# Adafruit_Speaker_Bonnet_rev_C.net
KiCad netlist of a schematic drawn in EAGLE
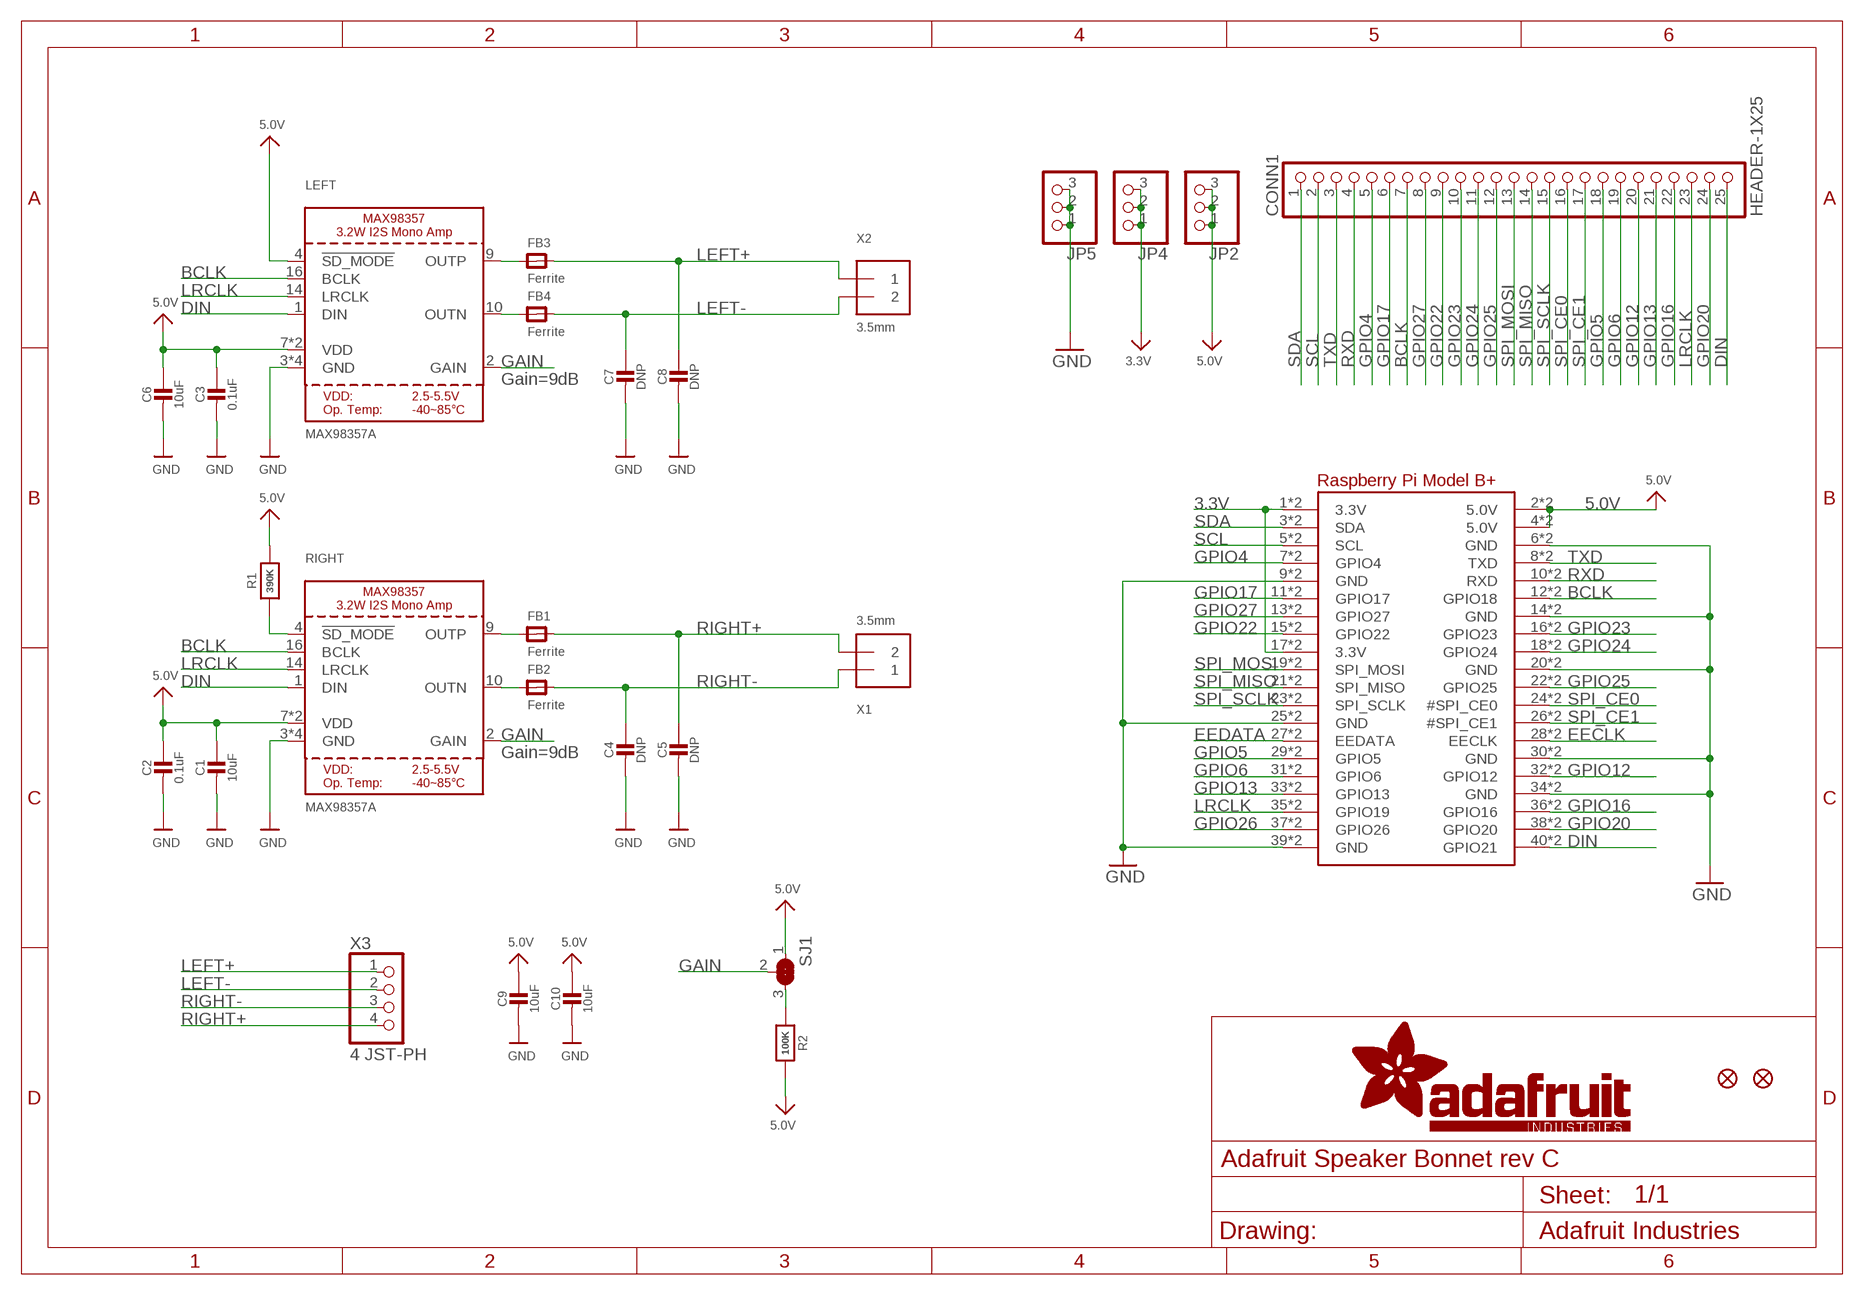
[diagram p0: schematic, sheet 1]

(export (version "E")
  (design (tool "Eeschema 10.0.6"))
  (components
    (comp (ref "C1")
      (value "10uF")
      (footprint "eagle-import:0805-NO")
      (libsource (lib "eagle-import") (part "CAP_CERAMIC0805-NOOUTLINE"))
    )
    (comp (ref "C2")
      (value "0.1uF")
      (footprint "eagle-import:0805-NO")
      (libsource (lib "eagle-import") (part "CAP_CERAMIC0805-NOOUTLINE"))
    )
    (comp (ref "C3")
      (value "0.1uF")
      (footprint "eagle-import:0805-NO")
      (libsource (lib "eagle-import") (part "CAP_CERAMIC0805-NOOUTLINE"))
    )
    (comp (ref "C4")
      (value "DNP")
      (footprint "eagle-import:0805-NO")
      (libsource (lib "eagle-import") (part "CAP_CERAMIC0805-NOOUTLINE"))
    )
    (comp (ref "C5")
      (value "DNP")
      (footprint "eagle-import:0805-NO")
      (libsource (lib "eagle-import") (part "CAP_CERAMIC0805-NOOUTLINE"))
    )
    (comp (ref "C6")
      (value "10uF")
      (footprint "eagle-import:0805-NO")
      (libsource (lib "eagle-import") (part "CAP_CERAMIC0805-NOOUTLINE"))
    )
    (comp (ref "C7")
      (value "DNP")
      (footprint "eagle-import:0805-NO")
      (libsource (lib "eagle-import") (part "CAP_CERAMIC0805-NOOUTLINE"))
    )
    (comp (ref "C8")
      (value "DNP")
      (footprint "eagle-import:0805-NO")
      (libsource (lib "eagle-import") (part "CAP_CERAMIC0805-NOOUTLINE"))
    )
    (comp (ref "C9")
      (value "10uF")
      (footprint "eagle-import:0805-NO")
      (libsource (lib "eagle-import") (part "CAP_CERAMIC0805-NOOUTLINE"))
    )
    (comp (ref "C10")
      (value "10uF")
      (footprint "eagle-import:0805-NO")
      (libsource (lib "eagle-import") (part "CAP_CERAMIC0805-NOOUTLINE"))
    )
    (comp (ref "CONN1")
      (value "HEADER-1X25")
      (footprint "eagle-import:1X25_ROUND_70MIL")
      (libsource (lib "eagle-import") (part "HEADER-1X25"))
    )
    (comp (ref "FB1")
      (value "Ferrite")
      (footprint "eagle-import:0805-NO")
      (libsource (lib "eagle-import") (part "FERRITE-0805NO"))
    )
    (comp (ref "FB2")
      (value "Ferrite")
      (footprint "eagle-import:0805-NO")
      (libsource (lib "eagle-import") (part "FERRITE-0805NO"))
    )
    (comp (ref "FB3")
      (value "Ferrite")
      (footprint "eagle-import:0805-NO")
      (libsource (lib "eagle-import") (part "FERRITE-0805NO"))
    )
    (comp (ref "FB4")
      (value "Ferrite")
      (footprint "eagle-import:0805-NO")
      (libsource (lib "eagle-import") (part "FERRITE-0805NO"))
    )
    (comp (ref "FID1")
      (value "FIDUCIAL_1MM")
      (footprint "eagle-import:FIDUCIAL_1MM")
      (libsource (lib "eagle-import") (part "FIDUCIAL_1MM"))
    )
    (comp (ref "FID2")
      (value "FIDUCIAL_1MM")
      (footprint "eagle-import:FIDUCIAL_1MM")
      (libsource (lib "eagle-import") (part "FIDUCIAL_1MM"))
    )
    (comp (ref "JP2")
      (value "HEADER-1X376MIL")
      (footprint "eagle-import:1X03_ROUND_76")
      (libsource (lib "eagle-import") (part "HEADER-1X376MIL"))
    )
    (comp (ref "JP4")
      (value "HEADER-1X376MIL")
      (footprint "eagle-import:1X03_ROUND_76")
      (libsource (lib "eagle-import") (part "HEADER-1X376MIL"))
    )
    (comp (ref "JP5")
      (value "HEADER-1X376MIL")
      (footprint "eagle-import:1X03_ROUND_76")
      (libsource (lib "eagle-import") (part "HEADER-1X376MIL"))
    )
    (comp (ref "LEFT")
      (value "MAX98357A")
      (footprint "eagle-import:QFN16_3MM")
      (libsource (lib "eagle-import") (part "AUDIOAMP_MAX98357"))
    )
    (comp (ref "R1")
      (value "390K")
      (footprint "eagle-import:0805-NO")
      (libsource (lib "eagle-import") (part "RESISTOR0805_NOOUTLINE"))
    )
    (comp (ref "R2")
      (value "100K")
      (footprint "eagle-import:0805-NO")
      (libsource (lib "eagle-import") (part "RESISTOR0805_NOOUTLINE"))
    )
    (comp (ref "RIGHT")
      (value "MAX98357A")
      (footprint "eagle-import:QFN16_3MM")
      (libsource (lib "eagle-import") (part "AUDIOAMP_MAX98357"))
    )
    (comp (ref "RPI1")
      (value "RASPBERRYPI_BPLUS_BONNET_THMSMT")
      (footprint "eagle-import:PI_BONNET_THMSMT")
      (libsource (lib "eagle-import") (part "RASPBERRYPI_BPLUS_BONNET_THMSMT"))
    )
    (comp (ref "SJ1")
      (value "SOLDERJUMPER_2WAY")
      (footprint "eagle-import:SOLDERJUMPER_2WAY_OPEN_NOPASTE")
      (libsource (lib "eagle-import") (part "SOLDERJUMPER_2WAY"))
    )
    (comp (ref "X1")
      (value "3.5mm")
      (footprint "eagle-import:TERMBLOCK_1X2-3.5MM")
      (libsource (lib "eagle-import") (part "TERMBLOCK_1X2"))
    )
    (comp (ref "X2")
      (value "3.5mm")
      (footprint "eagle-import:TERMBLOCK_1X2-3.5MM")
      (libsource (lib "eagle-import") (part "TERMBLOCK_1X2"))
    )
    (comp (ref "X3")
      (value "4 JST-PH")
      (footprint "eagle-import:JSTPH4")
      (libsource (lib "eagle-import") (part "CON_JST_PH_4PIN"))
    )
  )
  (nets
    (net (code "1") (name "/BCLK") (class "Default")
      (node (ref "CONN1") (pin "7") (pinfunction "7_7") (pintype "passive"))
      (node (ref "LEFT") (pin "16") (pinfunction "BCLK_16") (pintype "bidirectional"))
      (node (ref "RIGHT") (pin "16") (pinfunction "BCLK_16") (pintype "bidirectional"))
      (node (ref "RPI1") (pin "12") (pinfunction "GPIO18_12") (pintype "bidirectional"))
      (node (ref "RPI1") (pin "S12") (pinfunction "GPIO18_S12") (pintype "bidirectional"))
    )
    (net (code "2") (name "/DIN") (class "Default")
      (node (ref "CONN1") (pin "25") (pinfunction "25_25") (pintype "passive"))
      (node (ref "LEFT") (pin "1") (pinfunction "DIN_1") (pintype "bidirectional"))
      (node (ref "RIGHT") (pin "1") (pinfunction "DIN_1") (pintype "bidirectional"))
      (node (ref "RPI1") (pin "40") (pinfunction "GPIO21_40") (pintype "bidirectional"))
      (node (ref "RPI1") (pin "S40") (pinfunction "GPIO21_S40") (pintype "bidirectional"))
    )
    (net (code "3") (name "/EECLK") (class "Default")
      (node (ref "RPI1") (pin "28") (pinfunction "EECLK_28") (pintype "bidirectional"))
      (node (ref "RPI1") (pin "S28") (pinfunction "EECLK_S28") (pintype "bidirectional"))
    )
    (net (code "4") (name "/EEDATA") (class "Default")
      (node (ref "RPI1") (pin "27") (pinfunction "EEDATA_27") (pintype "bidirectional"))
      (node (ref "RPI1") (pin "S27") (pinfunction "EEDATA_S27") (pintype "bidirectional"))
    )
    (net (code "5") (name "/GAIN") (class "Default")
      (node (ref "LEFT") (pin "2") (pinfunction "GAIN_2") (pintype "bidirectional"))
      (node (ref "RIGHT") (pin "2") (pinfunction "GAIN_2") (pintype "bidirectional"))
      (node (ref "SJ1") (pin "2") (pinfunction "2_2") (pintype "passive"))
    )
    (net (code "6") (name "/GPIO4") (class "Default")
      (node (ref "CONN1") (pin "5") (pinfunction "5_5") (pintype "passive"))
      (node (ref "RPI1") (pin "7") (pinfunction "GPIO4_7") (pintype "bidirectional"))
      (node (ref "RPI1") (pin "S7") (pinfunction "GPIO4_S7") (pintype "bidirectional"))
    )
    (net (code "7") (name "/GPIO5") (class "Default")
      (node (ref "CONN1") (pin "18") (pinfunction "18_18") (pintype "passive"))
      (node (ref "RPI1") (pin "29") (pinfunction "GPIO5_29") (pintype "bidirectional"))
      (node (ref "RPI1") (pin "S29") (pinfunction "GPIO5_S29") (pintype "bidirectional"))
    )
    (net (code "8") (name "/GPIO6") (class "Default")
      (node (ref "CONN1") (pin "19") (pinfunction "19_19") (pintype "passive"))
      (node (ref "RPI1") (pin "31") (pinfunction "GPIO6_31") (pintype "bidirectional"))
      (node (ref "RPI1") (pin "S31") (pinfunction "GPIO6_S31") (pintype "bidirectional"))
    )
    (net (code "9") (name "/GPIO12") (class "Default")
      (node (ref "CONN1") (pin "20") (pinfunction "20_20") (pintype "passive"))
      (node (ref "RPI1") (pin "32") (pinfunction "GPIO12_32") (pintype "bidirectional"))
      (node (ref "RPI1") (pin "S32") (pinfunction "GPIO12_S32") (pintype "bidirectional"))
    )
    (net (code "10") (name "/GPIO13") (class "Default")
      (node (ref "CONN1") (pin "21") (pinfunction "21_21") (pintype "passive"))
      (node (ref "RPI1") (pin "33") (pinfunction "GPIO13_33") (pintype "bidirectional"))
      (node (ref "RPI1") (pin "S33") (pinfunction "GPIO13_S33") (pintype "bidirectional"))
    )
    (net (code "11") (name "/GPIO16") (class "Default")
      (node (ref "CONN1") (pin "22") (pinfunction "22_22") (pintype "passive"))
      (node (ref "RPI1") (pin "36") (pinfunction "GPIO16_36") (pintype "bidirectional"))
      (node (ref "RPI1") (pin "S36") (pinfunction "GPIO16_S36") (pintype "bidirectional"))
    )
    (net (code "12") (name "/GPIO17") (class "Default")
      (node (ref "CONN1") (pin "6") (pinfunction "6_6") (pintype "passive"))
      (node (ref "RPI1") (pin "11") (pinfunction "GPIO17_11") (pintype "bidirectional"))
      (node (ref "RPI1") (pin "S11") (pinfunction "GPIO17_S11") (pintype "bidirectional"))
    )
    (net (code "13") (name "/GPIO20") (class "Default")
      (node (ref "CONN1") (pin "24") (pinfunction "24_24") (pintype "passive"))
      (node (ref "RPI1") (pin "38") (pinfunction "GPIO20_38") (pintype "bidirectional"))
      (node (ref "RPI1") (pin "S38") (pinfunction "GPIO20_S38") (pintype "bidirectional"))
    )
    (net (code "14") (name "/GPIO22") (class "Default")
      (node (ref "CONN1") (pin "9") (pinfunction "9_9") (pintype "passive"))
      (node (ref "RPI1") (pin "15") (pinfunction "GPIO22_15") (pintype "bidirectional"))
      (node (ref "RPI1") (pin "S15") (pinfunction "GPIO22_S15") (pintype "bidirectional"))
    )
    (net (code "15") (name "/GPIO23") (class "Default")
      (node (ref "CONN1") (pin "10") (pinfunction "10_10") (pintype "passive"))
      (node (ref "RPI1") (pin "16") (pinfunction "GPIO23_16") (pintype "bidirectional"))
      (node (ref "RPI1") (pin "S16") (pinfunction "GPIO23_S16") (pintype "bidirectional"))
    )
    (net (code "16") (name "/GPIO24") (class "Default")
      (node (ref "CONN1") (pin "11") (pinfunction "11_11") (pintype "passive"))
      (node (ref "RPI1") (pin "18") (pinfunction "GPIO24_18") (pintype "bidirectional"))
      (node (ref "RPI1") (pin "S18") (pinfunction "GPIO24_S18") (pintype "bidirectional"))
    )
    (net (code "17") (name "/GPIO25") (class "Default")
      (node (ref "CONN1") (pin "12") (pinfunction "12_12") (pintype "passive"))
      (node (ref "RPI1") (pin "22") (pinfunction "GPIO25_22") (pintype "bidirectional"))
      (node (ref "RPI1") (pin "S22") (pinfunction "GPIO25_S22") (pintype "bidirectional"))
    )
    (net (code "18") (name "/GPIO26") (class "Default")
      (node (ref "RPI1") (pin "37") (pinfunction "GPIO26_37") (pintype "bidirectional"))
      (node (ref "RPI1") (pin "S37") (pinfunction "GPIO26_S37") (pintype "bidirectional"))
    )
    (net (code "19") (name "/GPIO27") (class "Default")
      (node (ref "CONN1") (pin "8") (pinfunction "8_8") (pintype "passive"))
      (node (ref "RPI1") (pin "13") (pinfunction "GPIO27_13") (pintype "bidirectional"))
      (node (ref "RPI1") (pin "S13") (pinfunction "GPIO27_S13") (pintype "bidirectional"))
    )
    (net (code "20") (name "/LEFT+") (class "Default")
      (node (ref "C8") (pin "1") (pinfunction "1_1") (pintype "passive"))
      (node (ref "FB3") (pin "2") (pinfunction "P$2_2") (pintype "passive"))
      (node (ref "X2") (pin "1") (pinfunction "1_1") (pintype "passive"))
      (node (ref "X3") (pin "1") (pinfunction "1_1") (pintype "passive"))
    )
    (net (code "21") (name "/LEFT-") (class "Default")
      (node (ref "C7") (pin "1") (pinfunction "1_1") (pintype "passive"))
      (node (ref "FB4") (pin "2") (pinfunction "P$2_2") (pintype "passive"))
      (node (ref "X2") (pin "2") (pinfunction "2_2") (pintype "passive"))
      (node (ref "X3") (pin "2") (pinfunction "2_2") (pintype "passive"))
    )
    (net (code "22") (name "/LRCLK") (class "Default")
      (node (ref "CONN1") (pin "23") (pinfunction "23_23") (pintype "passive"))
      (node (ref "LEFT") (pin "14") (pinfunction "LRCLK_14") (pintype "bidirectional"))
      (node (ref "RIGHT") (pin "14") (pinfunction "LRCLK_14") (pintype "bidirectional"))
      (node (ref "RPI1") (pin "35") (pinfunction "GPIO19_35") (pintype "bidirectional"))
      (node (ref "RPI1") (pin "S35") (pinfunction "GPIO19_S35") (pintype "bidirectional"))
    )
    (net (code "23") (name "/RIGHT+") (class "Default")
      (node (ref "C5") (pin "1") (pinfunction "1_1") (pintype "passive"))
      (node (ref "FB1") (pin "2") (pinfunction "P$2_2") (pintype "passive"))
      (node (ref "X1") (pin "2") (pinfunction "2_2") (pintype "passive"))
      (node (ref "X3") (pin "4") (pinfunction "4_4") (pintype "passive"))
    )
    (net (code "24") (name "/RIGHT-") (class "Default")
      (node (ref "C4") (pin "1") (pinfunction "1_1") (pintype "passive"))
      (node (ref "FB2") (pin "2") (pinfunction "P$2_2") (pintype "passive"))
      (node (ref "X1") (pin "1") (pinfunction "1_1") (pintype "passive"))
      (node (ref "X3") (pin "3") (pinfunction "3_3") (pintype "passive"))
    )
    (net (code "25") (name "/RXD") (class "Default")
      (node (ref "CONN1") (pin "4") (pinfunction "4_4") (pintype "passive"))
      (node (ref "RPI1") (pin "10") (pinfunction "RXD_10") (pintype "bidirectional"))
      (node (ref "RPI1") (pin "S10") (pinfunction "RXD_S10") (pintype "bidirectional"))
    )
    (net (code "26") (name "/SCL") (class "Default")
      (node (ref "CONN1") (pin "2") (pinfunction "2_2") (pintype "passive"))
      (node (ref "RPI1") (pin "5") (pinfunction "SCL_5") (pintype "bidirectional"))
      (node (ref "RPI1") (pin "S5") (pinfunction "SCL_S5") (pintype "bidirectional"))
    )
    (net (code "27") (name "/SDA") (class "Default")
      (node (ref "CONN1") (pin "1") (pinfunction "1_1") (pintype "passive"))
      (node (ref "RPI1") (pin "3") (pinfunction "SDA_3") (pintype "bidirectional"))
      (node (ref "RPI1") (pin "S3") (pinfunction "SDA_S3") (pintype "bidirectional"))
    )
    (net (code "28") (name "/SPI_CE0") (class "Default")
      (node (ref "CONN1") (pin "16") (pinfunction "16_16") (pintype "passive"))
      (node (ref "RPI1") (pin "24") (pinfunction "#SPI_CE0_24") (pintype "bidirectional"))
      (node (ref "RPI1") (pin "S24") (pinfunction "#SPI_CE0_S24") (pintype "bidirectional"))
    )
    (net (code "29") (name "/SPI_CE1") (class "Default")
      (node (ref "CONN1") (pin "17") (pinfunction "17_17") (pintype "passive"))
      (node (ref "RPI1") (pin "26") (pinfunction "#SPI_CE1_26") (pintype "bidirectional"))
      (node (ref "RPI1") (pin "S26") (pinfunction "#SPI_CE1_S26") (pintype "bidirectional"))
    )
    (net (code "30") (name "/SPI_MISO") (class "Default")
      (node (ref "CONN1") (pin "14") (pinfunction "14_14") (pintype "passive"))
      (node (ref "RPI1") (pin "21") (pinfunction "SPI_MISO_21") (pintype "bidirectional"))
      (node (ref "RPI1") (pin "S21") (pinfunction "SPI_MISO_S21") (pintype "bidirectional"))
    )
    (net (code "31") (name "/SPI_MOSI") (class "Default")
      (node (ref "CONN1") (pin "13") (pinfunction "13_13") (pintype "passive"))
      (node (ref "RPI1") (pin "19") (pinfunction "SPI_MOSI_19") (pintype "bidirectional"))
      (node (ref "RPI1") (pin "S19") (pinfunction "SPI_MOSI_S19") (pintype "bidirectional"))
    )
    (net (code "32") (name "/SPI_SCLK") (class "Default")
      (node (ref "CONN1") (pin "15") (pinfunction "15_15") (pintype "passive"))
      (node (ref "RPI1") (pin "23") (pinfunction "SPI_SCLK_23") (pintype "bidirectional"))
      (node (ref "RPI1") (pin "S23") (pinfunction "SPI_SCLK_S23") (pintype "bidirectional"))
    )
    (net (code "33") (name "/TXD") (class "Default")
      (node (ref "CONN1") (pin "3") (pinfunction "3_3") (pintype "passive"))
      (node (ref "RPI1") (pin "8") (pinfunction "TXD_8") (pintype "bidirectional"))
      (node (ref "RPI1") (pin "S8") (pinfunction "TXD_S8") (pintype "bidirectional"))
    )
    (net (code "34") (name "3.3V") (class "Default")
      (node (ref "JP4") (pin "1") (pinfunction "1_1") (pintype "passive"))
      (node (ref "JP4") (pin "2") (pinfunction "2_2") (pintype "passive"))
      (node (ref "JP4") (pin "3") (pinfunction "3_3") (pintype "passive"))
      (node (ref "RPI1") (pin "1") (pinfunction "3.3V_1") (pintype "power_in"))
      (node (ref "RPI1") (pin "17") (pinfunction "3.3V_17") (pintype "power_in"))
      (node (ref "RPI1") (pin "S1") (pinfunction "3.3V_S1") (pintype "power_in"))
      (node (ref "RPI1") (pin "S17") (pinfunction "3.3V_S17") (pintype "power_in"))
    )
    (net (code "35") (name "5.0V") (class "Default")
      (node (ref "C1") (pin "1") (pinfunction "1_1") (pintype "passive"))
      (node (ref "C10") (pin "1") (pinfunction "1_1") (pintype "passive"))
      (node (ref "C2") (pin "1") (pinfunction "1_1") (pintype "passive"))
      (node (ref "C3") (pin "1") (pinfunction "1_1") (pintype "passive"))
      (node (ref "C6") (pin "1") (pinfunction "1_1") (pintype "passive"))
      (node (ref "C9") (pin "1") (pinfunction "1_1") (pintype "passive"))
      (node (ref "JP2") (pin "1") (pinfunction "1_1") (pintype "passive"))
      (node (ref "JP2") (pin "2") (pinfunction "2_2") (pintype "passive"))
      (node (ref "JP2") (pin "3") (pinfunction "3_3") (pintype "passive"))
      (node (ref "LEFT") (pin "4") (pinfunction "~{SD_MODE}_4") (pintype "bidirectional"))
      (node (ref "LEFT") (pin "7") (pinfunction "VDD_7") (pintype "power_in"))
      (node (ref "LEFT") (pin "8") (pinfunction "VDD_8") (pintype "power_in"))
      (node (ref "R1") (pin "2") (pinfunction "2_2") (pintype "passive"))
      (node (ref "R2") (pin "2") (pinfunction "2_2") (pintype "passive"))
      (node (ref "RIGHT") (pin "7") (pinfunction "VDD_7") (pintype "power_in"))
      (node (ref "RIGHT") (pin "8") (pinfunction "VDD_8") (pintype "power_in"))
      (node (ref "RPI1") (pin "2") (pinfunction "5.0V_2") (pintype "power_in"))
      (node (ref "RPI1") (pin "4") (pinfunction "5.0V_4") (pintype "power_in"))
      (node (ref "RPI1") (pin "S2") (pinfunction "5.0V_S2") (pintype "power_in"))
      (node (ref "RPI1") (pin "S4") (pinfunction "5.0V_S4") (pintype "power_in"))
      (node (ref "SJ1") (pin "1") (pinfunction "1_1") (pintype "passive"))
    )
    (net (code "36") (name "GND") (class "Default")
      (node (ref "C1") (pin "2") (pinfunction "2_2") (pintype "passive"))
      (node (ref "C10") (pin "2") (pinfunction "2_2") (pintype "passive"))
      (node (ref "C2") (pin "2") (pinfunction "2_2") (pintype "passive"))
      (node (ref "C3") (pin "2") (pinfunction "2_2") (pintype "passive"))
      (node (ref "C4") (pin "2") (pinfunction "2_2") (pintype "passive"))
      (node (ref "C5") (pin "2") (pinfunction "2_2") (pintype "passive"))
      (node (ref "C6") (pin "2") (pinfunction "2_2") (pintype "passive"))
      (node (ref "C7") (pin "2") (pinfunction "2_2") (pintype "passive"))
      (node (ref "C8") (pin "2") (pinfunction "2_2") (pintype "passive"))
      (node (ref "C9") (pin "2") (pinfunction "2_2") (pintype "passive"))
      (node (ref "JP5") (pin "1") (pinfunction "1_1") (pintype "passive"))
      (node (ref "JP5") (pin "2") (pinfunction "2_2") (pintype "passive"))
      (node (ref "JP5") (pin "3") (pinfunction "3_3") (pintype "passive"))
      (node (ref "LEFT") (pin "11") (pinfunction "GND_11") (pintype "power_in"))
      (node (ref "LEFT") (pin "15") (pinfunction "GND_15") (pintype "power_in"))
      (node (ref "LEFT") (pin "3") (pinfunction "GND_3") (pintype "power_in"))
      (node (ref "LEFT") (pin "THERMAL") (pinfunction "GND_THERMAL") (pintype "power_in"))
      (node (ref "RIGHT") (pin "11") (pinfunction "GND_11") (pintype "power_in"))
      (node (ref "RIGHT") (pin "15") (pinfunction "GND_15") (pintype "power_in"))
      (node (ref "RIGHT") (pin "3") (pinfunction "GND_3") (pintype "power_in"))
      (node (ref "RIGHT") (pin "THERMAL") (pinfunction "GND_THERMAL") (pintype "power_in"))
      (node (ref "RPI1") (pin "14") (pinfunction "GND_14") (pintype "power_in"))
      (node (ref "RPI1") (pin "20") (pinfunction "GND_20") (pintype "power_in"))
      (node (ref "RPI1") (pin "25") (pinfunction "GND_25") (pintype "power_in"))
      (node (ref "RPI1") (pin "30") (pinfunction "GND_30") (pintype "power_in"))
      (node (ref "RPI1") (pin "34") (pinfunction "GND_34") (pintype "power_in"))
      (node (ref "RPI1") (pin "39") (pinfunction "GND_39") (pintype "power_in"))
      (node (ref "RPI1") (pin "6") (pinfunction "GND_6") (pintype "power_in"))
      (node (ref "RPI1") (pin "9") (pinfunction "GND_9") (pintype "power_in"))
      (node (ref "RPI1") (pin "S14") (pinfunction "GND_S14") (pintype "power_in"))
      (node (ref "RPI1") (pin "S20") (pinfunction "GND_S20") (pintype "power_in"))
      (node (ref "RPI1") (pin "S25") (pinfunction "GND_S25") (pintype "power_in"))
      (node (ref "RPI1") (pin "S30") (pinfunction "GND_S30") (pintype "power_in"))
      (node (ref "RPI1") (pin "S34") (pinfunction "GND_S34") (pintype "power_in"))
      (node (ref "RPI1") (pin "S39") (pinfunction "GND_S39") (pintype "power_in"))
      (node (ref "RPI1") (pin "S6") (pinfunction "GND_S6") (pintype "power_in"))
      (node (ref "RPI1") (pin "S9") (pinfunction "GND_S9") (pintype "power_in"))
    )
    (net (code "37") (name "Net-(FB1-P$1)") (class "Default")
      (node (ref "FB1") (pin "1") (pinfunction "P$1_1") (pintype "passive"))
      (node (ref "RIGHT") (pin "9") (pinfunction "OUTP_9") (pintype "output"))
    )
    (net (code "38") (name "Net-(FB2-P$1)") (class "Default")
      (node (ref "FB2") (pin "1") (pinfunction "P$1_1") (pintype "passive"))
      (node (ref "RIGHT") (pin "10") (pinfunction "OUTN_10") (pintype "output"))
    )
    (net (code "39") (name "Net-(FB3-P$1)") (class "Default")
      (node (ref "FB3") (pin "1") (pinfunction "P$1_1") (pintype "passive"))
      (node (ref "LEFT") (pin "9") (pinfunction "OUTP_9") (pintype "output"))
    )
    (net (code "40") (name "Net-(FB4-P$1)") (class "Default")
      (node (ref "FB4") (pin "1") (pinfunction "P$1_1") (pintype "passive"))
      (node (ref "LEFT") (pin "10") (pinfunction "OUTN_10") (pintype "output"))
    )
    (net (code "41") (name "Net-(R2-Pad1)") (class "Default")
      (node (ref "R2") (pin "1") (pinfunction "1_1") (pintype "passive"))
      (node (ref "SJ1") (pin "3") (pinfunction "3_3") (pintype "passive"))
    )
    (net (code "42") (name "Net-(RIGHT-~{SD_MODE})") (class "Default")
      (node (ref "R1") (pin "1") (pinfunction "1_1") (pintype "passive"))
      (node (ref "RIGHT") (pin "4") (pinfunction "~{SD_MODE}_4") (pintype "bidirectional"))
    )
  )
)
